# Connectors.net
KiCad netlist of a schematic drawn in Altium Designer
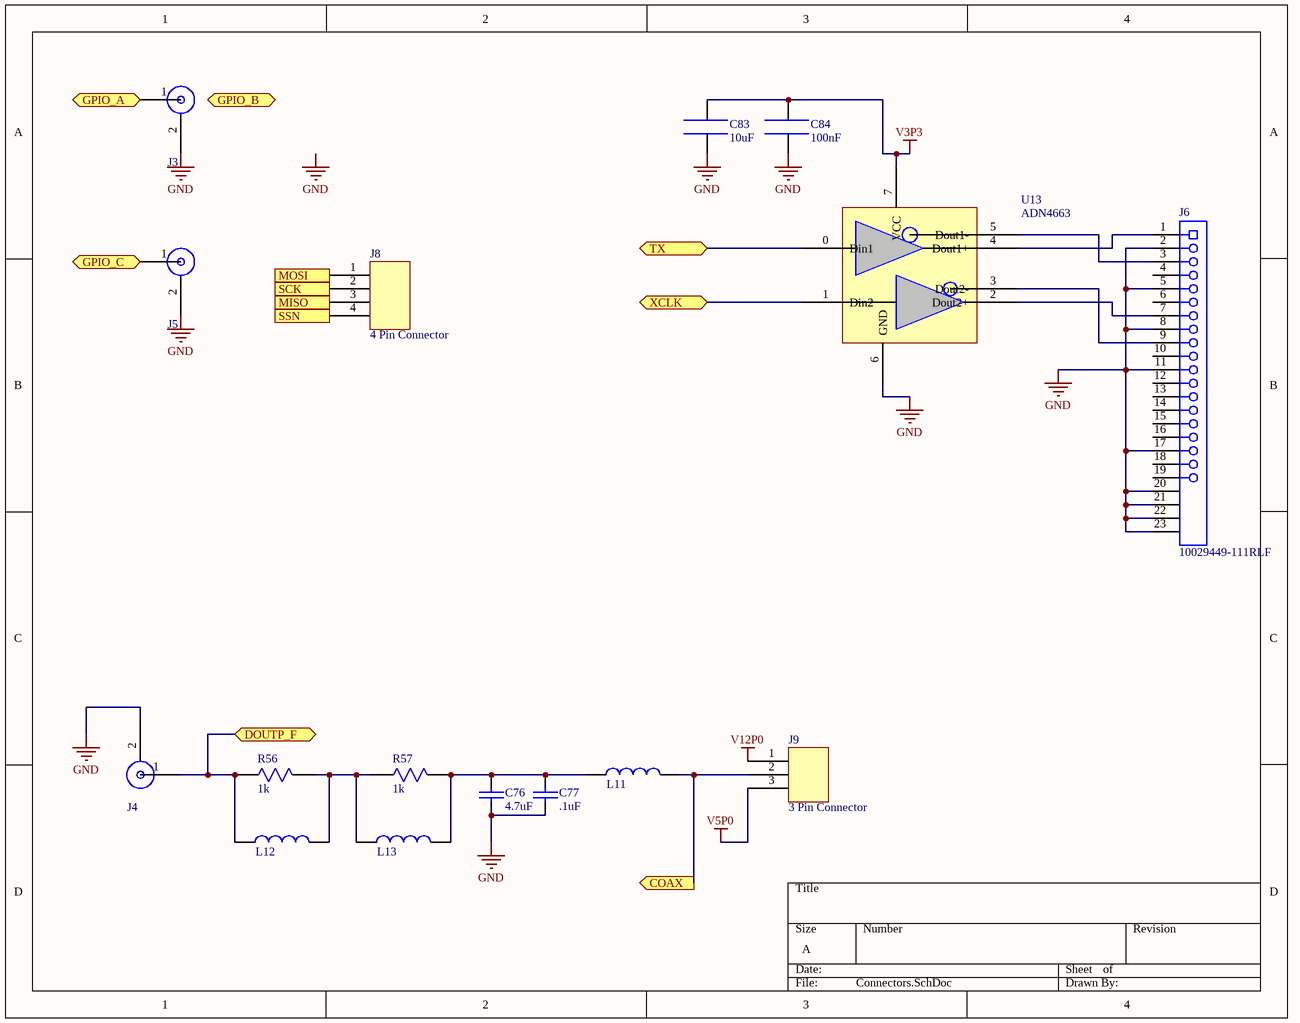
[diagram p0: Connectors.SchDoc]

(export (version "E")
  (design (tool "Eeschema 10.0.6"))
  (components
    (comp (ref "C76")
      (value "4.7uF")
      (footprint "SMD Capacitor 0603")
      (libsource (lib "") (part "Capacitor_1"))
    )
    (comp (ref "C77") (value ".1uF") (footprint "SMD CAP 0402") (libsource (lib "") (part "Capacitor_1")))
    (comp (ref "C83")
      (value "10uF")
      (footprint "SMD Capacitor 0603")
      (fields (field (name "Comment") "Capacitor"))
      (libsource (lib "DA_Component_Library") (part "Capacitor"))
    )
    (comp (ref "C84")
      (value "100nF")
      (footprint "SMD Capacitor 0603")
      (fields (field (name "Comment") "Capacitor"))
      (libsource (lib "DA_Component_Library") (part "Capacitor"))
    )
    (comp (ref "J3")
      (value "SMA")
      (footprint "SMA Right Angle Through Hole")
      (libsource (lib "DA_Component_Library") (part "SMA"))
    )
    (comp (ref "J4")
      (value "SMA")
      (footprint "SMA Right Angle Through Hole")
      (libsource (lib "DA_Component_Library") (part "SMA"))
    )
    (comp (ref "J5")
      (value "SMA")
      (footprint "SMA Right Angle Through Hole")
      (libsource (lib "DA_Component_Library") (part "SMA"))
    )
    (comp (ref "J6")
      (value "10029449-111RLF")
      (footprint "FCI-10029449-111RLF_V")
      (fields (field (name "MANUFACTURER") "FCI"))
      (libsource (lib "Altium Content Vault") (part "CN-1P-F-HD19"))
    )
    (comp (ref "J8")
      (value "4 Pin Connector")
      (footprint "4Pin Verital 0.1\"")
      (libsource (lib "DA_Component_Library") (part "4 Pin Connector"))
    )
    (comp (ref "J9")
      (value "3 Pin Connector")
      (footprint "3Pin Verital 0.1\" JUMOER")
      (libsource (lib "DA_Component_Library") (part "3 Pin Connector"))
    )
    (comp (ref "L11")
      (value "Ferrite Bead")
      (footprint "BLM18KG601SN1D")
      (libsource (lib "DA_Component_Library") (part "Ferrite Bead"))
    )
    (comp (ref "L12")
      (value "Ferrite Bead")
      (footprint "CIG21L4R7MNE")
      (libsource (lib "DA_Component_Library") (part "Ferrite Bead"))
    )
    (comp (ref "L13")
      (value "Ferrite Bead")
      (footprint "CBC3225T101MR")
      (libsource (lib "DA_Component_Library") (part "Ferrite Bead"))
    )
    (comp (ref "R56")
      (value "1k")
      (footprint "SMD Resistor 0603")
      (libsource (lib "DA_Component_Library") (part "Resistor"))
    )
    (comp (ref "R57")
      (value "1k")
      (footprint "SMD Resistor 0603")
      (libsource (lib "DA_Component_Library") (part "Resistor"))
    )
    (comp (ref "U13")
      (value "ADN4663")
      (footprint "SOIC127P600X175-8N")
      (libsource (lib "Integrated_Library1") (part "DUAL_LVDS_TX"))
    )
  )
  (nets
    (net (code "1") (name "/COAX") (class "Default")
      (node (ref "J9") (pin "2") (pinfunction "2_2") (pintype "passive"))
      (node (ref "L11") (pin "2") (pinfunction "2_2") (pintype "passive"))
    )
    (net (code "2") (name "/DOUTP_F") (class "Default")
      (node (ref "J4") (pin "1") (pinfunction "1_1") (pintype "passive"))
      (node (ref "L12") (pin "1") (pinfunction "1_1") (pintype "passive"))
      (node (ref "R56") (pin "0") (pinfunction "0_0") (pintype "passive"))
    )
    (net (code "3") (name "/GPIO_A") (class "Default")
      (node (ref "J3") (pin "1") (pinfunction "1_1") (pintype "passive"))
    )
    (net (code "5") (name "/GPIO_C") (class "Default")
      (node (ref "J5") (pin "1") (pinfunction "1_1") (pintype "passive"))
    )
    (net (code "6") (name "/MISO") (class "Default")
      (node (ref "J8") (pin "3") (pinfunction "3_3") (pintype "passive"))
    )
    (net (code "7") (name "/MOSI") (class "Default")
      (node (ref "J8") (pin "1") (pinfunction "1_1") (pintype "passive"))
    )
    (net (code "8") (name "/SCK") (class "Default")
      (node (ref "J8") (pin "2") (pinfunction "2_2") (pintype "passive"))
    )
    (net (code "9") (name "/SSN") (class "Default")
      (node (ref "J8") (pin "4") (pinfunction "4_4") (pintype "passive"))
    )
    (net (code "10") (name "/TX") (class "Default")
      (node (ref "U13") (pin "0") (pinfunction "Din1_0") (pintype "passive"))
    )
    (net (code "11") (name "/XCLK") (class "Default")
      (node (ref "U13") (pin "1") (pinfunction "Din2_1") (pintype "passive"))
    )
    (net (code "12") (name "GND") (class "Default")
      (node (ref "C76") (pin "1") (pinfunction "1_1") (pintype "passive"))
      (node (ref "C77") (pin "1") (pinfunction "1_1") (pintype "passive"))
      (node (ref "C83") (pin "0") (pinfunction "0_0") (pintype "passive"))
      (node (ref "C84") (pin "0") (pinfunction "0_0") (pintype "passive"))
      (node (ref "J3") (pin "2") (pinfunction "2_2") (pintype "passive"))
      (node (ref "J4") (pin "2") (pinfunction "2_2") (pintype "passive"))
      (node (ref "J5") (pin "2") (pinfunction "2_2") (pintype "passive"))
      (node (ref "J6") (pin "11") (pinfunction "11_11") (pintype "passive"))
      (node (ref "J6") (pin "17") (pinfunction "17_17") (pintype "passive"))
      (node (ref "J6") (pin "2") (pinfunction "2_2") (pintype "passive"))
      (node (ref "J6") (pin "20") (pinfunction "SHLD1_20") (pintype "passive"))
      (node (ref "J6") (pin "21") (pinfunction "SHLD2_21") (pintype "passive"))
      (node (ref "J6") (pin "22") (pinfunction "SHLD3_22") (pintype "passive"))
      (node (ref "J6") (pin "23") (pinfunction "SHLD4_23") (pintype "passive"))
      (node (ref "J6") (pin "5") (pinfunction "5_5") (pintype "passive"))
      (node (ref "J6") (pin "8") (pinfunction "8_8") (pintype "passive"))
      (node (ref "U13") (pin "6") (pinfunction "GND_6") (pintype "passive"))
    )
    (net (code "13") (name "Net-(C76-Pad0)") (class "Default")
      (node (ref "C76") (pin "0") (pinfunction "0_0") (pintype "passive"))
      (node (ref "C77") (pin "0") (pinfunction "0_0") (pintype "passive"))
      (node (ref "L11") (pin "1") (pinfunction "1_1") (pintype "passive"))
      (node (ref "L13") (pin "2") (pinfunction "2_2") (pintype "passive"))
      (node (ref "R57") (pin "1") (pinfunction "1_1") (pintype "passive"))
    )
    (net (code "14") (name "Net-(L12-Pad2)") (class "Default")
      (node (ref "L12") (pin "2") (pinfunction "2_2") (pintype "passive"))
      (node (ref "L13") (pin "1") (pinfunction "1_1") (pintype "passive"))
      (node (ref "R56") (pin "1") (pinfunction "1_1") (pintype "passive"))
      (node (ref "R57") (pin "0") (pinfunction "0_0") (pintype "passive"))
    )
    (net (code "15") (name "Net-(U13-Dout1+)") (class "Default")
      (node (ref "J6") (pin "1") (pinfunction "1_1") (pintype "passive"))
      (node (ref "U13") (pin "4") (pinfunction "Dout1+_4") (pintype "passive"))
    )
    (net (code "16") (name "Net-(U13-Dout1-)") (class "Default")
      (node (ref "J6") (pin "3") (pinfunction "3_3") (pintype "passive"))
      (node (ref "U13") (pin "5") (pinfunction "Dout1-_5") (pintype "passive"))
    )
    (net (code "17") (name "Net-(U13-Dout2+)") (class "Default")
      (node (ref "J6") (pin "7") (pinfunction "7_7") (pintype "passive"))
      (node (ref "U13") (pin "2") (pinfunction "Dout2+_2") (pintype "passive"))
    )
    (net (code "18") (name "Net-(U13-Dout2-)") (class "Default")
      (node (ref "J6") (pin "9") (pinfunction "9_9") (pintype "passive"))
      (node (ref "U13") (pin "3") (pinfunction "Dout2-_3") (pintype "passive"))
    )
    (net (code "19") (name "V3P3") (class "Default")
      (node (ref "C83") (pin "1") (pinfunction "1_1") (pintype "passive"))
      (node (ref "C84") (pin "1") (pinfunction "1_1") (pintype "passive"))
      (node (ref "U13") (pin "7") (pinfunction "VCC_7") (pintype "passive"))
    )
    (net (code "20") (name "V5P0") (class "Default")
      (node (ref "J9") (pin "3") (pinfunction "3_3") (pintype "passive"))
    )
    (net (code "21") (name "V12P0") (class "Default")
      (node (ref "J9") (pin "1") (pinfunction "1_1") (pintype "passive"))
    )
    (net (code "22") (name "unconnected-(J6-Pad4)") (class "Default")
      (node (ref "J6") (pin "4") (pinfunction "4_4") (pintype "passive"))
    )
    (net (code "23") (name "unconnected-(J6-Pad6)") (class "Default")
      (node (ref "J6") (pin "6") (pinfunction "6_6") (pintype "passive"))
    )
    (net (code "24") (name "unconnected-(J6-Pad10)") (class "Default")
      (node (ref "J6") (pin "10") (pinfunction "10_10") (pintype "passive"))
    )
    (net (code "25") (name "unconnected-(J6-Pad12)") (class "Default")
      (node (ref "J6") (pin "12") (pinfunction "12_12") (pintype "passive"))
    )
    (net (code "26") (name "unconnected-(J6-Pad13)") (class "Default")
      (node (ref "J6") (pin "13") (pinfunction "13_13") (pintype "passive"))
    )
    (net (code "27") (name "unconnected-(J6-Pad14)") (class "Default")
      (node (ref "J6") (pin "14") (pinfunction "14_14") (pintype "passive"))
    )
    (net (code "28") (name "unconnected-(J6-Pad15)") (class "Default")
      (node (ref "J6") (pin "15") (pinfunction "15_15") (pintype "passive"))
    )
    (net (code "29") (name "unconnected-(J6-Pad16)") (class "Default")
      (node (ref "J6") (pin "16") (pinfunction "16_16") (pintype "passive"))
    )
    (net (code "30") (name "unconnected-(J6-Pad18)") (class "Default")
      (node (ref "J6") (pin "18") (pinfunction "18_18") (pintype "passive"))
    )
    (net (code "31") (name "unconnected-(J6-Pad19)") (class "Default")
      (node (ref "J6") (pin "19") (pinfunction "19_19") (pintype "passive"))
    )
  )
)
